# ratio.net
KiCad netlist of a schematic drawn in EAGLE
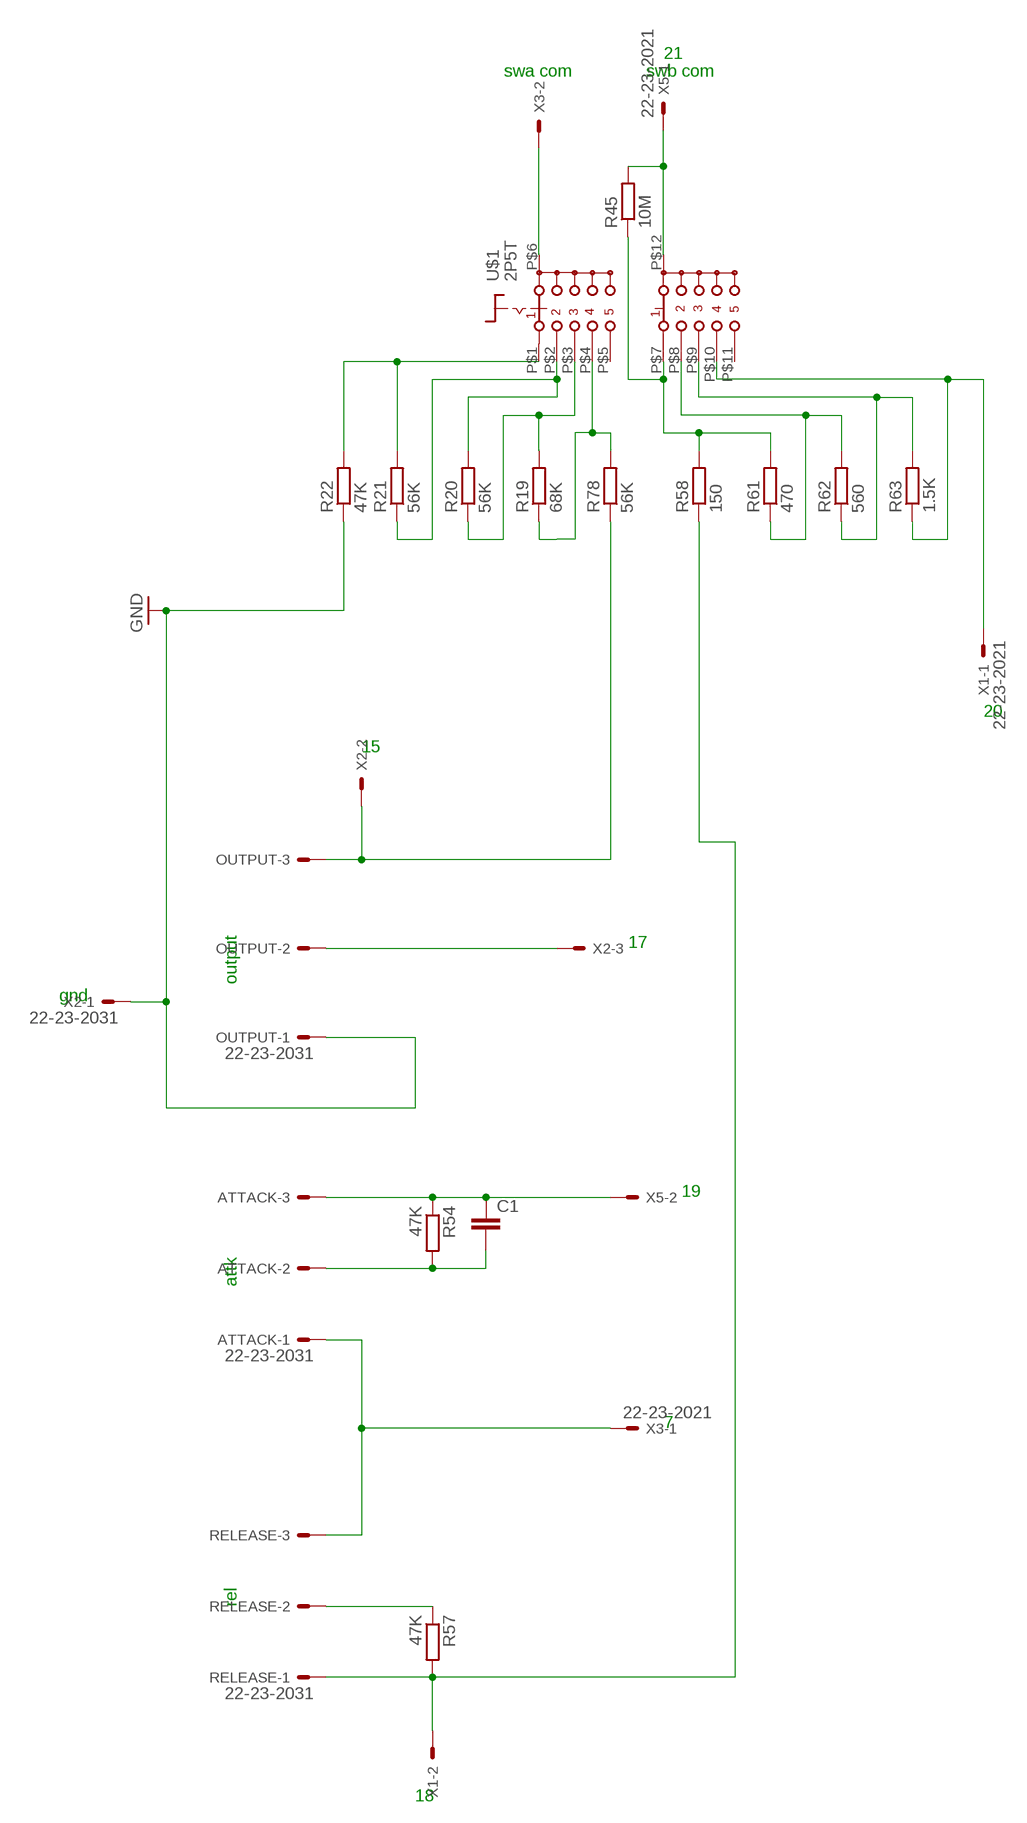
[diagram p0: schematic, sheet 1]

(export (version "E")
  (design (tool "Eeschema 10.0.6"))
  (components
    (comp (ref "ATTACK")
      (value "22-23-2031")
      (footprint "eagle-import:22-23-2031")
      (fields (field (name "MF") "MOLEX"))
      (libsource (lib "eagle-import") (part "22-23-2031"))
    )
    (comp (ref "C1")
      (value "C-EU025-025X050")
      (footprint "eagle-import:C025-025X050")
      (libsource (lib "eagle-import") (part "C-EU025-025X050"))
    )
    (comp (ref "OUTPUT")
      (value "22-23-2031")
      (footprint "eagle-import:22-23-2031")
      (fields (field (name "MF") "MOLEX"))
      (libsource (lib "eagle-import") (part "22-23-2031"))
    )
    (comp (ref "R19")
      (value "68K")
      (footprint "eagle-import:0204V")
      (libsource (lib "eagle-import") (part "R-EU_0204/2V"))
    )
    (comp (ref "R20")
      (value "56K")
      (footprint "eagle-import:0204V")
      (libsource (lib "eagle-import") (part "R-EU_0204/2V"))
    )
    (comp (ref "R21")
      (value "56K")
      (footprint "eagle-import:0204V")
      (libsource (lib "eagle-import") (part "R-EU_0204/2V"))
    )
    (comp (ref "R22")
      (value "47K")
      (footprint "eagle-import:0204V")
      (libsource (lib "eagle-import") (part "R-EU_0204/2V"))
    )
    (comp (ref "R45")
      (value "10M")
      (footprint "eagle-import:0204V")
      (libsource (lib "eagle-import") (part "R-EU_0204/2V"))
    )
    (comp (ref "R54")
      (value "47K")
      (footprint "eagle-import:0204V")
      (libsource (lib "eagle-import") (part "R-EU_0204/2V"))
    )
    (comp (ref "R57")
      (value "47K")
      (footprint "eagle-import:0204V")
      (libsource (lib "eagle-import") (part "R-EU_0204/2V"))
    )
    (comp (ref "R58")
      (value "150")
      (footprint "eagle-import:0204V")
      (libsource (lib "eagle-import") (part "R-EU_0204/2V"))
    )
    (comp (ref "R61")
      (value "470")
      (footprint "eagle-import:0204V")
      (libsource (lib "eagle-import") (part "R-EU_0204/2V"))
    )
    (comp (ref "R62")
      (value "560")
      (footprint "eagle-import:0204V")
      (libsource (lib "eagle-import") (part "R-EU_0204/2V"))
    )
    (comp (ref "R63")
      (value "1.5K")
      (footprint "eagle-import:0204V")
      (libsource (lib "eagle-import") (part "R-EU_0204/2V"))
    )
    (comp (ref "R78")
      (value "56K")
      (footprint "eagle-import:0204V")
      (libsource (lib "eagle-import") (part "R-EU_0204/2V"))
    )
    (comp (ref "RELEASE")
      (value "22-23-2031")
      (footprint "eagle-import:22-23-2031")
      (fields (field (name "MF") "MOLEX"))
      (libsource (lib "eagle-import") (part "22-23-2031"))
    )
    (comp (ref "U$1")
      (value "2P5T")
      (footprint "eagle-import:2P5T")
      (libsource (lib "eagle-import") (part "2P5T"))
    )
    (comp (ref "X1")
      (value "22-23-2021")
      (footprint "eagle-import:22-23-2021")
      (fields (field (name "MF") "MOLEX"))
      (libsource (lib "eagle-import") (part "22-23-2021"))
    )
    (comp (ref "X2")
      (value "22-23-2031")
      (footprint "eagle-import:22-23-2031")
      (fields (field (name "MF") "MOLEX"))
      (libsource (lib "eagle-import") (part "22-23-2031"))
    )
    (comp (ref "X3")
      (value "22-23-2021")
      (footprint "eagle-import:22-23-2021")
      (fields (field (name "MF") "MOLEX"))
      (libsource (lib "eagle-import") (part "22-23-2021"))
    )
    (comp (ref "X5")
      (value "22-23-2021")
      (footprint "eagle-import:22-23-2021")
      (fields (field (name "MF") "MOLEX"))
      (libsource (lib "eagle-import") (part "22-23-2021"))
    )
  )
  (nets
    (net (code "1") (name "GND") (class "Default")
      (node (ref "OUTPUT") (pin "1") (pinfunction "S_1") (pintype "passive"))
      (node (ref "R22") (pin "1") (pinfunction "1_1") (pintype "passive"))
      (node (ref "X2") (pin "1") (pinfunction "S_1") (pintype "passive"))
    )
    (net (code "2") (name "Net-(ATTACKA-S)") (class "Default")
      (node (ref "ATTACK") (pin "1") (pinfunction "S_1") (pintype "passive"))
      (node (ref "RELEASE") (pin "3") (pinfunction "S_3") (pintype "passive"))
      (node (ref "X3") (pin "1") (pinfunction "S_1") (pintype "passive"))
    )
    (net (code "3") (name "Net-(ATTACKB-S)") (class "Default")
      (node (ref "ATTACK") (pin "2") (pinfunction "S_2") (pintype "passive"))
      (node (ref "C1") (pin "2") (pinfunction "2_2") (pintype "passive"))
      (node (ref "R54") (pin "2") (pinfunction "2_2") (pintype "passive"))
    )
    (net (code "4") (name "Net-(ATTACKC-S)") (class "Default")
      (node (ref "ATTACK") (pin "3") (pinfunction "S_3") (pintype "passive"))
      (node (ref "C1") (pin "1") (pinfunction "1_1") (pintype "passive"))
      (node (ref "R54") (pin "1") (pinfunction "1_1") (pintype "passive"))
      (node (ref "X5") (pin "2") (pinfunction "S_2") (pintype "passive"))
    )
    (net (code "5") (name "Net-(OUTPUTB-S)") (class "Default")
      (node (ref "OUTPUT") (pin "2") (pinfunction "S_2") (pintype "passive"))
      (node (ref "X2") (pin "3") (pinfunction "S_3") (pintype "passive"))
    )
    (net (code "6") (name "Net-(OUTPUTC-S)") (class "Default")
      (node (ref "OUTPUT") (pin "3") (pinfunction "S_3") (pintype "passive"))
      (node (ref "R78") (pin "1") (pinfunction "1_1") (pintype "passive"))
      (node (ref "X2") (pin "2") (pinfunction "S_2") (pintype "passive"))
    )
    (net (code "7") (name "Net-(RELEASEA-S)") (class "Default")
      (node (ref "R57") (pin "2") (pinfunction "2_2") (pintype "passive"))
      (node (ref "R58") (pin "1") (pinfunction "1_1") (pintype "passive"))
      (node (ref "RELEASE") (pin "1") (pinfunction "S_1") (pintype "passive"))
      (node (ref "X1") (pin "2") (pinfunction "S_2") (pintype "passive"))
    )
    (net (code "8") (name "Net-(RELEASEB-S)") (class "Default")
      (node (ref "R57") (pin "1") (pinfunction "1_1") (pintype "passive"))
      (node (ref "RELEASE") (pin "2") (pinfunction "S_2") (pintype "passive"))
    )
    (net (code "9") (name "Net-(U$1-A)") (class "Default")
      (node (ref "U$1") (pin "P$6") (pinfunction "A_P$6") (pintype "passive"))
      (node (ref "X3") (pin "2") (pinfunction "S_2") (pintype "passive"))
    )
    (net (code "10") (name "Net-(U$1-A1)") (class "Default")
      (node (ref "R21") (pin "2") (pinfunction "2_2") (pintype "passive"))
      (node (ref "R22") (pin "2") (pinfunction "2_2") (pintype "passive"))
      (node (ref "U$1") (pin "P$1") (pinfunction "A1_P$1") (pintype "passive"))
    )
    (net (code "11") (name "Net-(U$1-A2)") (class "Default")
      (node (ref "R20") (pin "2") (pinfunction "2_2") (pintype "passive"))
      (node (ref "R21") (pin "1") (pinfunction "1_1") (pintype "passive"))
      (node (ref "U$1") (pin "P$2") (pinfunction "A2_P$2") (pintype "passive"))
    )
    (net (code "12") (name "Net-(U$1-A3)") (class "Default")
      (node (ref "R19") (pin "2") (pinfunction "2_2") (pintype "passive"))
      (node (ref "R20") (pin "1") (pinfunction "1_1") (pintype "passive"))
      (node (ref "U$1") (pin "P$3") (pinfunction "A3_P$3") (pintype "passive"))
    )
    (net (code "13") (name "Net-(U$1-A4)") (class "Default")
      (node (ref "R19") (pin "1") (pinfunction "1_1") (pintype "passive"))
      (node (ref "R78") (pin "2") (pinfunction "2_2") (pintype "passive"))
      (node (ref "U$1") (pin "P$4") (pinfunction "A4_P$4") (pintype "passive"))
    )
    (net (code "14") (name "Net-(U$1-C)") (class "Default")
      (node (ref "R45") (pin "2") (pinfunction "2_2") (pintype "passive"))
      (node (ref "U$1") (pin "P$12") (pinfunction "C_P$12") (pintype "passive"))
      (node (ref "X5") (pin "1") (pinfunction "S_1") (pintype "passive"))
    )
    (net (code "15") (name "Net-(U$1-C1)") (class "Default")
      (node (ref "R45") (pin "1") (pinfunction "1_1") (pintype "passive"))
      (node (ref "R58") (pin "2") (pinfunction "2_2") (pintype "passive"))
      (node (ref "R61") (pin "2") (pinfunction "2_2") (pintype "passive"))
      (node (ref "U$1") (pin "P$7") (pinfunction "C1_P$7") (pintype "passive"))
    )
    (net (code "16") (name "Net-(U$1-C2)") (class "Default")
      (node (ref "R61") (pin "1") (pinfunction "1_1") (pintype "passive"))
      (node (ref "R62") (pin "2") (pinfunction "2_2") (pintype "passive"))
      (node (ref "U$1") (pin "P$8") (pinfunction "C2_P$8") (pintype "passive"))
    )
    (net (code "17") (name "Net-(U$1-C3)") (class "Default")
      (node (ref "R62") (pin "1") (pinfunction "1_1") (pintype "passive"))
      (node (ref "R63") (pin "2") (pinfunction "2_2") (pintype "passive"))
      (node (ref "U$1") (pin "P$9") (pinfunction "C3_P$9") (pintype "passive"))
    )
    (net (code "18") (name "Net-(U$1-C4)") (class "Default")
      (node (ref "R63") (pin "1") (pinfunction "1_1") (pintype "passive"))
      (node (ref "U$1") (pin "P$10") (pinfunction "C4_P$10") (pintype "passive"))
      (node (ref "X1") (pin "1") (pinfunction "S_1") (pintype "passive"))
    )
    (net (code "19") (name "unconnected-(U$1-A5-PadP$5)") (class "Default")
      (node (ref "U$1") (pin "P$5") (pinfunction "A5_P$5") (pintype "passive"))
    )
    (net (code "20") (name "unconnected-(U$1-C5-PadP$11)") (class "Default")
      (node (ref "U$1") (pin "P$11") (pinfunction "C5_P$11") (pintype "passive"))
    )
  )
)
